# MEMORIES.net
KiCad netlist of a schematic drawn in Altium Designer
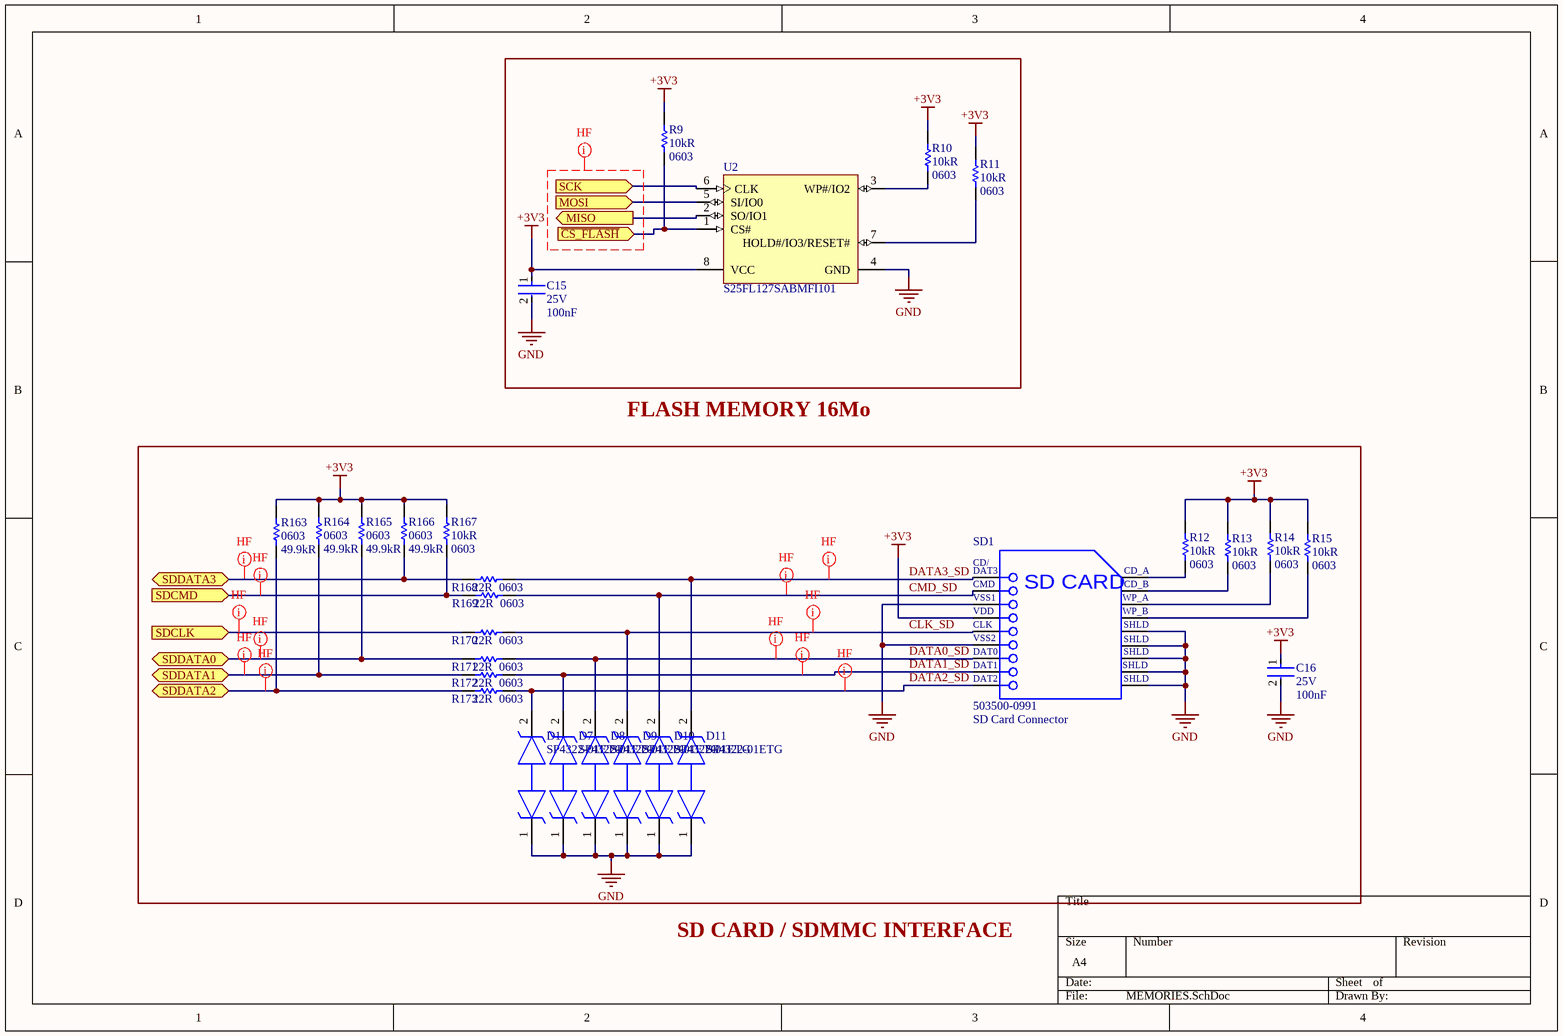
[diagram p0: MEMORIES.SchDoc]

(export (version "E")
  (design (tool "Eeschema 10.0.6"))
  (components
    (comp (ref "C15")
      (value "CGA3E2X7R1E104K080AA")
      (footprint "FP-CGA3E-0_3-0_1-MFG")
      (description "Cap Ceramic 100nF 25V X7R 10% Pad SMD 0603 +125°C Automotive T/R")
      (fields
        (field (name "VOLTAGE RATING (DC)") "25V")
        (field (name "CAPACITANCE") "100nF")
        (field (name "TOLERANCE") "10%")
        (field (name "MANUFACTURER") "TDK")
      )
      (libsource (lib "Altium Content Vault") (part "b4654b650e69147ec39a6b967a45e02"))
    )
    (comp (ref "C16")
      (value "CGA3E2X7R1E104K080AA")
      (footprint "FP-CGA3E-0_3-0_1-MFG")
      (description "Cap Ceramic 100nF 25V X7R 10% Pad SMD 0603 +125°C Automotive T/R")
      (fields
        (field (name "VOLTAGE RATING (DC)") "25V")
        (field (name "CAPACITANCE") "100nF")
        (field (name "TOLERANCE") "10%")
        (field (name "MANUFACTURER") "TDK")
      )
      (libsource (lib "Altium Content Vault") (part "b4654b650e69147ec39a6b967a45e02"))
    )
    (comp (ref "D1")
      (value "SP4322-01ETG")
      (footprint "SamacSys:SP432201ETG")
      (description "TVS Diode (Bi-directional)")
      (fields (field (name "MOUSER PART NUMBER") "576-SP4322-01ETG"))
      (libsource (lib "*") (part "SP4322-01ETG"))
    )
    (comp (ref "D7")
      (value "SP4322-01ETG")
      (footprint "SamacSys:SP432201ETG")
      (description "TVS Diode (Bi-directional)")
      (fields (field (name "MOUSER PART NUMBER") "576-SP4322-01ETG"))
      (libsource (lib "*") (part "SP4322-01ETG"))
    )
    (comp (ref "D8")
      (value "SP4322-01ETG")
      (footprint "SamacSys:SP432201ETG")
      (description "TVS Diode (Bi-directional)")
      (fields (field (name "MOUSER PART NUMBER") "576-SP4322-01ETG"))
      (libsource (lib "*") (part "SP4322-01ETG"))
    )
    (comp (ref "D9")
      (value "SP4322-01ETG")
      (footprint "SamacSys:SP432201ETG")
      (description "TVS Diode (Bi-directional)")
      (fields (field (name "MOUSER PART NUMBER") "576-SP4322-01ETG"))
      (libsource (lib "*") (part "SP4322-01ETG"))
    )
    (comp (ref "D10")
      (value "SP4322-01ETG")
      (footprint "SamacSys:SP432201ETG")
      (description "TVS Diode (Bi-directional)")
      (fields (field (name "MOUSER PART NUMBER") "576-SP4322-01ETG"))
      (libsource (lib "*") (part "SP4322-01ETG"))
    )
    (comp (ref "D11")
      (value "SP4322-01ETG")
      (footprint "SamacSys:SP432201ETG")
      (description "TVS Diode (Bi-directional)")
      (fields (field (name "MOUSER PART NUMBER") "576-SP4322-01ETG"))
      (libsource (lib "*") (part "SP4322-01ETG"))
    )
    (comp (ref "R9")
      (value "ERJ3EKF1002V")
      (footprint "RESC1609X55X30LL15T15")
      (description "Chip Resistor, 10 KOhm, +/- 1%, 0.1 W, -55 to 155 degC, 0603 (1608 Metric), RoHS, Tape and Reel")
      (fields
        (field (name "RESISTANCE") "10kR")
        (field (name "CASE CODE (IMPERIAL)") "0603")
        (field (name "TOLERANCE") "1%")
        (field (name "MANUFACTURER") "Panasonic")
      )
      (libsource (lib "Altium Content Vault") (part "RES-2"))
    )
    (comp (ref "R10")
      (value "ERJ3EKF1002V")
      (footprint "RESC1609X55X30LL15T15")
      (description "Chip Resistor, 10 KOhm, +/- 1%, 0.1 W, -55 to 155 degC, 0603 (1608 Metric), RoHS, Tape and Reel")
      (fields
        (field (name "RESISTANCE") "10kR")
        (field (name "CASE CODE (IMPERIAL)") "0603")
        (field (name "TOLERANCE") "1%")
        (field (name "MANUFACTURER") "Panasonic")
      )
      (libsource (lib "Altium Content Vault") (part "RES-2"))
    )
    (comp (ref "R11")
      (value "ERJ3EKF1002V")
      (footprint "RESC1609X55X30LL15T15")
      (description "Chip Resistor, 10 KOhm, +/- 1%, 0.1 W, -55 to 155 degC, 0603 (1608 Metric), RoHS, Tape and Reel")
      (fields
        (field (name "RESISTANCE") "10kR")
        (field (name "CASE CODE (IMPERIAL)") "0603")
        (field (name "TOLERANCE") "1%")
        (field (name "MANUFACTURER") "Panasonic")
      )
      (libsource (lib "Altium Content Vault") (part "RES-2"))
    )
    (comp (ref "R12")
      (value "ERJ3EKF1002V")
      (footprint "RESC1609X55X30LL15T15")
      (description "Chip Resistor, 10 KOhm, +/- 1%, 0.1 W, -55 to 155 degC, 0603 (1608 Metric), RoHS, Tape and Reel")
      (fields
        (field (name "RESISTANCE") "10kR")
        (field (name "CASE CODE (IMPERIAL)") "0603")
        (field (name "TOLERANCE") "1%")
        (field (name "MANUFACTURER") "Panasonic")
      )
      (libsource (lib "Altium Content Vault") (part "RES-2"))
    )
    (comp (ref "R13")
      (value "ERJ3EKF1002V")
      (footprint "RESC1609X55X30LL15T15")
      (description "Chip Resistor, 10 KOhm, +/- 1%, 0.1 W, -55 to 155 degC, 0603 (1608 Metric), RoHS, Tape and Reel")
      (fields
        (field (name "RESISTANCE") "10kR")
        (field (name "CASE CODE (IMPERIAL)") "0603")
        (field (name "TOLERANCE") "1%")
        (field (name "MANUFACTURER") "Panasonic")
      )
      (libsource (lib "Altium Content Vault") (part "RES-2"))
    )
    (comp (ref "R14")
      (value "ERJ3EKF1002V")
      (footprint "RESC1609X55X30LL15T15")
      (description "Chip Resistor, 10 KOhm, +/- 1%, 0.1 W, -55 to 155 degC, 0603 (1608 Metric), RoHS, Tape and Reel")
      (fields
        (field (name "RESISTANCE") "10kR")
        (field (name "CASE CODE (IMPERIAL)") "0603")
        (field (name "TOLERANCE") "1%")
        (field (name "MANUFACTURER") "Panasonic")
      )
      (libsource (lib "Altium Content Vault") (part "RES-2"))
    )
    (comp (ref "R15")
      (value "ERJ3EKF1002V")
      (footprint "RESC1609X55X30LL15T15")
      (description "Chip Resistor, 10 KOhm, +/- 1%, 0.1 W, -55 to 155 degC, 0603 (1608 Metric), RoHS, Tape and Reel")
      (fields
        (field (name "RESISTANCE") "10kR")
        (field (name "CASE CODE (IMPERIAL)") "0603")
        (field (name "TOLERANCE") "1%")
        (field (name "MANUFACTURER") "Panasonic")
      )
      (libsource (lib "Altium Content Vault") (part "RES-2"))
    )
    (comp (ref "R163")
      (value "ERJ-3EKF4992V")
      (footprint "RESC1608X55X30ML15T15")
      (fields
        (field (name "MANUFACTURER") "Panasonic")
        (field (name "CASE CODE (IMPERIAL)") "0603")
        (field (name "RESISTANCE") "49.9kR")
        (field (name "TOLERANCE") "1%")
      )
      (libsource (lib "Altium Content Vault") (part "RES"))
    )
    (comp (ref "R164")
      (value "ERJ-3EKF4992V")
      (footprint "RESC1608X55X30ML15T15")
      (fields
        (field (name "MANUFACTURER") "Panasonic")
        (field (name "CASE CODE (IMPERIAL)") "0603")
        (field (name "RESISTANCE") "49.9kR")
        (field (name "TOLERANCE") "1%")
      )
      (libsource (lib "Altium Content Vault") (part "RES"))
    )
    (comp (ref "R165")
      (value "ERJ-3EKF4992V")
      (footprint "RESC1608X55X30ML15T15")
      (fields
        (field (name "MANUFACTURER") "Panasonic")
        (field (name "CASE CODE (IMPERIAL)") "0603")
        (field (name "RESISTANCE") "49.9kR")
        (field (name "TOLERANCE") "1%")
      )
      (libsource (lib "Altium Content Vault") (part "RES"))
    )
    (comp (ref "R166")
      (value "ERJ-3EKF4992V")
      (footprint "RESC1608X55X30ML15T15")
      (fields
        (field (name "MANUFACTURER") "Panasonic")
        (field (name "CASE CODE (IMPERIAL)") "0603")
        (field (name "RESISTANCE") "49.9kR")
        (field (name "TOLERANCE") "1%")
      )
      (libsource (lib "Altium Content Vault") (part "RES"))
    )
    (comp (ref "R167")
      (value "ERJ3EKF1002V")
      (footprint "RESC1609X55X30LL15T15")
      (description "Chip Resistor, 10 KOhm, +/- 1%, 0.1 W, -55 to 155 degC, 0603 (1608 Metric), RoHS, Tape and Reel")
      (fields
        (field (name "RESISTANCE") "10kR")
        (field (name "CASE CODE (IMPERIAL)") "0603")
        (field (name "TOLERANCE") "1%")
        (field (name "MANUFACTURER") "Panasonic")
      )
      (libsource (lib "Altium Content Vault") (part "RES-2"))
    )
    (comp (ref "R168")
      (value "ERJ-3EKF22R0V")
      (footprint "RESC1608X55X30LL15T15")
      (description "Chip Resistor, 22 Ohm, +/- 1%, 0.1 W, -55 to 155 degC, 0603 (1608 Metric), RoHS, Tape and Reel")
      (fields
        (field (name "MANUFACTURER") "Panasonic")
        (field (name "MANUFACTURER PART NUMBER") "ERJ3EKF22R0V")
        (field (name "CASE CODE (IMPERIAL)") "0603")
        (field (name "RESISTANCE") "22R")
      )
      (libsource (lib "Altium Content Vault") (part "RES-2"))
    )
    (comp (ref "R169")
      (value "ERJ-3EKF22R0V")
      (footprint "RESC1608X55X30LL15T15")
      (description "Chip Resistor, 22 Ohm, +/- 1%, 0.1 W, -55 to 155 degC, 0603 (1608 Metric), RoHS, Tape and Reel")
      (fields
        (field (name "MANUFACTURER") "Panasonic")
        (field (name "MANUFACTURER PART NUMBER") "ERJ3EKF22R0V")
        (field (name "CASE CODE (IMPERIAL)") "0603")
        (field (name "RESISTANCE") "22R")
      )
      (libsource (lib "Altium Content Vault") (part "RES-2"))
    )
    (comp (ref "R170")
      (value "ERJ-3EKF22R0V")
      (footprint "RESC1608X55X30LL15T15")
      (description "Chip Resistor, 22 Ohm, +/- 1%, 0.1 W, -55 to 155 degC, 0603 (1608 Metric), RoHS, Tape and Reel")
      (fields
        (field (name "MANUFACTURER") "Panasonic")
        (field (name "MANUFACTURER PART NUMBER") "ERJ3EKF22R0V")
        (field (name "CASE CODE (IMPERIAL)") "0603")
        (field (name "RESISTANCE") "22R")
      )
      (libsource (lib "Altium Content Vault") (part "RES-2"))
    )
    (comp (ref "R171")
      (value "ERJ-3EKF22R0V")
      (footprint "RESC1608X55X30LL15T15")
      (description "Chip Resistor, 22 Ohm, +/- 1%, 0.1 W, -55 to 155 degC, 0603 (1608 Metric), RoHS, Tape and Reel")
      (fields
        (field (name "MANUFACTURER") "Panasonic")
        (field (name "MANUFACTURER PART NUMBER") "ERJ3EKF22R0V")
        (field (name "CASE CODE (IMPERIAL)") "0603")
        (field (name "RESISTANCE") "22R")
      )
      (libsource (lib "Altium Content Vault") (part "RES-2"))
    )
    (comp (ref "R172")
      (value "ERJ-3EKF22R0V")
      (footprint "RESC1608X55X30LL15T15")
      (description "Chip Resistor, 22 Ohm, +/- 1%, 0.1 W, -55 to 155 degC, 0603 (1608 Metric), RoHS, Tape and Reel")
      (fields
        (field (name "MANUFACTURER") "Panasonic")
        (field (name "MANUFACTURER PART NUMBER") "ERJ3EKF22R0V")
        (field (name "CASE CODE (IMPERIAL)") "0603")
        (field (name "RESISTANCE") "22R")
      )
      (libsource (lib "Altium Content Vault") (part "RES-2"))
    )
    (comp (ref "R173")
      (value "ERJ-3EKF22R0V")
      (footprint "RESC1608X55X30LL15T15")
      (description "Chip Resistor, 22 Ohm, +/- 1%, 0.1 W, -55 to 155 degC, 0603 (1608 Metric), RoHS, Tape and Reel")
      (fields
        (field (name "MANUFACTURER") "Panasonic")
        (field (name "MANUFACTURER PART NUMBER") "ERJ3EKF22R0V")
        (field (name "CASE CODE (IMPERIAL)") "0603")
        (field (name "RESISTANCE") "22R")
      )
      (libsource (lib "Altium Content Vault") (part "RES-2"))
    )
    (comp (ref "SD1")
      (value "503500-0991")
      (footprint "MOLX-503500-0991_V")
      (description "SD and Combo Memory Card Connector, 9 Position Surface Mount, -25 to 85 degC, RoHS, Tape and Reel")
      (fields (field (name "PACKAGEDESCRIPTION") "SD Card Connector") (field (name "MANUFACTURER") "Molex"))
      (libsource (lib "Altium Content Vault") (part "CN-SD-9-4SW-5S"))
    )
    (comp (ref "U2")
      (value "S25FL127SABMFI101")
      (footprint "SPSN-SO-8_M")
      (fields (field (name "MANUFACTURER") "Spansion"))
      (libsource (lib "Altium Content Vault") (part "SPSN-S25FL127S-SO8"))
    )
  )
  (nets
    (net (code "1") (name "+3V3") (class "Default")
      (node (ref "C15") (pin "1") (pinfunction "1_1") (pintype "passive"))
      (node (ref "C16") (pin "1") (pinfunction "1_1") (pintype "passive"))
      (node (ref "R10") (pin "2") (pinfunction "2_2") (pintype "passive"))
      (node (ref "R11") (pin "2") (pinfunction "2_2") (pintype "passive"))
      (node (ref "R12") (pin "2") (pinfunction "2_2") (pintype "passive"))
      (node (ref "R13") (pin "2") (pinfunction "2_2") (pintype "passive"))
      (node (ref "R14") (pin "2") (pinfunction "2_2") (pintype "passive"))
      (node (ref "R15") (pin "2") (pinfunction "2_2") (pintype "passive"))
      (node (ref "R163") (pin "2") (pinfunction "2_2") (pintype "passive"))
      (node (ref "R164") (pin "2") (pinfunction "2_2") (pintype "passive"))
      (node (ref "R165") (pin "2") (pinfunction "2_2") (pintype "passive"))
      (node (ref "R166") (pin "2") (pinfunction "2_2") (pintype "passive"))
      (node (ref "R167") (pin "2") (pinfunction "2_2") (pintype "passive"))
      (node (ref "R9") (pin "2") (pinfunction "2_2") (pintype "passive"))
      (node (ref "SD1") (pin "4") (pinfunction "VDD_4") (pintype "passive"))
      (node (ref "U2") (pin "8") (pinfunction "VCC_8") (pintype "power_in"))
    )
    (net (code "2") (name "/CLK_SD") (class "Default")
      (node (ref "D9") (pin "2") (pinfunction "2_2") (pintype "passive"))
      (node (ref "R170") (pin "2") (pinfunction "2_2") (pintype "passive"))
      (node (ref "SD1") (pin "5") (pinfunction "CLK_5") (pintype "passive"))
    )
    (net (code "3") (name "/CMD_SD") (class "Default")
      (node (ref "D10") (pin "2") (pinfunction "2_2") (pintype "passive"))
      (node (ref "R169") (pin "2") (pinfunction "2_2") (pintype "passive"))
      (node (ref "SD1") (pin "2") (pinfunction "CMD_2") (pintype "passive"))
    )
    (net (code "4") (name "/CS_FLASH") (class "Default")
      (node (ref "R9") (pin "1") (pinfunction "1_1") (pintype "passive"))
      (node (ref "U2") (pin "1") (pinfunction "CS#_1") (pintype "input"))
    )
    (net (code "5") (name "/DATA0_SD") (class "Default")
      (node (ref "D8") (pin "2") (pinfunction "2_2") (pintype "passive"))
      (node (ref "R171") (pin "2") (pinfunction "2_2") (pintype "passive"))
      (node (ref "SD1") (pin "7") (pinfunction "DAT0_7") (pintype "passive"))
    )
    (net (code "6") (name "/DATA1_SD") (class "Default")
      (node (ref "D7") (pin "2") (pinfunction "2_2") (pintype "passive"))
      (node (ref "R172") (pin "2") (pinfunction "2_2") (pintype "passive"))
      (node (ref "SD1") (pin "8") (pinfunction "DAT1_8") (pintype "passive"))
    )
    (net (code "7") (name "/DATA2_SD") (class "Default")
      (node (ref "D1") (pin "2") (pinfunction "2_2") (pintype "passive"))
      (node (ref "R173") (pin "2") (pinfunction "2_2") (pintype "passive"))
      (node (ref "SD1") (pin "9") (pinfunction "DAT2_9") (pintype "passive"))
    )
    (net (code "8") (name "/DATA3_SD") (class "Default")
      (node (ref "D11") (pin "2") (pinfunction "2_2") (pintype "passive"))
      (node (ref "R168") (pin "2") (pinfunction "2_2") (pintype "passive"))
      (node (ref "SD1") (pin "1") (pinfunction "CD/DAT3_1") (pintype "passive"))
    )
    (net (code "9") (name "/MISO") (class "Default")
      (node (ref "U2") (pin "2") (pinfunction "SO/IO1_2") (pintype "bidirectional"))
    )
    (net (code "10") (name "/MOSI") (class "Default")
      (node (ref "U2") (pin "5") (pinfunction "SI/IO0_5") (pintype "bidirectional"))
    )
    (net (code "11") (name "/SCK") (class "Default")
      (node (ref "U2") (pin "6") (pinfunction "CLK_6") (pintype "input"))
    )
    (net (code "12") (name "/SDCLK") (class "Default")
      (node (ref "R170") (pin "1") (pinfunction "1_1") (pintype "passive"))
    )
    (net (code "13") (name "/SDCMD") (class "Default")
      (node (ref "R167") (pin "1") (pinfunction "1_1") (pintype "passive"))
      (node (ref "R169") (pin "1") (pinfunction "1_1") (pintype "passive"))
    )
    (net (code "14") (name "/SDDATA0") (class "Default")
      (node (ref "R165") (pin "1") (pinfunction "1_1") (pintype "passive"))
      (node (ref "R171") (pin "1") (pinfunction "1_1") (pintype "passive"))
    )
    (net (code "15") (name "/SDDATA1") (class "Default")
      (node (ref "R164") (pin "1") (pinfunction "1_1") (pintype "passive"))
      (node (ref "R172") (pin "1") (pinfunction "1_1") (pintype "passive"))
    )
    (net (code "16") (name "/SDDATA2") (class "Default")
      (node (ref "R163") (pin "1") (pinfunction "1_1") (pintype "passive"))
      (node (ref "R173") (pin "1") (pinfunction "1_1") (pintype "passive"))
    )
    (net (code "17") (name "/SDDATA3") (class "Default")
      (node (ref "R166") (pin "1") (pinfunction "1_1") (pintype "passive"))
      (node (ref "R168") (pin "1") (pinfunction "1_1") (pintype "passive"))
    )
    (net (code "18") (name "GND") (class "Default")
      (node (ref "C15") (pin "2") (pinfunction "2_2") (pintype "passive"))
      (node (ref "C16") (pin "2") (pinfunction "2_2") (pintype "passive"))
      (node (ref "D1") (pin "1") (pinfunction "1_1") (pintype "passive"))
      (node (ref "D10") (pin "1") (pinfunction "1_1") (pintype "passive"))
      (node (ref "D11") (pin "1") (pinfunction "1_1") (pintype "passive"))
      (node (ref "D7") (pin "1") (pinfunction "1_1") (pintype "passive"))
      (node (ref "D8") (pin "1") (pinfunction "1_1") (pintype "passive"))
      (node (ref "D9") (pin "1") (pinfunction "1_1") (pintype "passive"))
      (node (ref "SD1") (pin "14") (pinfunction "SHLD1_14") (pintype "passive"))
      (node (ref "SD1") (pin "15") (pinfunction "SHLD2_15") (pintype "passive"))
      (node (ref "SD1") (pin "16") (pinfunction "SHLD3_16") (pintype "passive"))
      (node (ref "SD1") (pin "17") (pinfunction "SHLD4_17") (pintype "passive"))
      (node (ref "SD1") (pin "18") (pinfunction "SHLD5_18") (pintype "passive"))
      (node (ref "SD1") (pin "3") (pinfunction "VSS1_3") (pintype "passive"))
      (node (ref "SD1") (pin "6") (pinfunction "VSS2_6") (pintype "passive"))
      (node (ref "U2") (pin "4") (pinfunction "GND_4") (pintype "power_in"))
    )
    (net (code "19") (name "Net-(SD1-CD_A)") (class "Default")
      (node (ref "R12") (pin "1") (pinfunction "1_1") (pintype "passive"))
      (node (ref "SD1") (pin "10") (pinfunction "CD_A_10") (pintype "passive"))
    )
    (net (code "20") (name "Net-(SD1-CD_B)") (class "Default")
      (node (ref "R13") (pin "1") (pinfunction "1_1") (pintype "passive"))
      (node (ref "SD1") (pin "11") (pinfunction "CD_B_11") (pintype "passive"))
    )
    (net (code "21") (name "Net-(SD1-WP_A)") (class "Default")
      (node (ref "R14") (pin "1") (pinfunction "1_1") (pintype "passive"))
      (node (ref "SD1") (pin "12") (pinfunction "WP_A_12") (pintype "passive"))
    )
    (net (code "22") (name "Net-(SD1-WP_B)") (class "Default")
      (node (ref "R15") (pin "1") (pinfunction "1_1") (pintype "passive"))
      (node (ref "SD1") (pin "13") (pinfunction "WP_B_13") (pintype "passive"))
    )
    (net (code "23") (name "Net-(U2-HOLD#{slash}IO3{slash}RESET#)") (class "Default")
      (node (ref "R11") (pin "1") (pinfunction "1_1") (pintype "passive"))
      (node (ref "U2") (pin "7") (pinfunction "HOLD#/IO3/RESET#_7") (pintype "bidirectional"))
    )
    (net (code "24") (name "Net-(U2-WP#{slash}IO2)") (class "Default")
      (node (ref "R10") (pin "1") (pinfunction "1_1") (pintype "passive"))
      (node (ref "U2") (pin "3") (pinfunction "WP#/IO2_3") (pintype "bidirectional"))
    )
  )
)
